# boilerroom.net
KiCad netlist of a schematic drawn in EAGLE
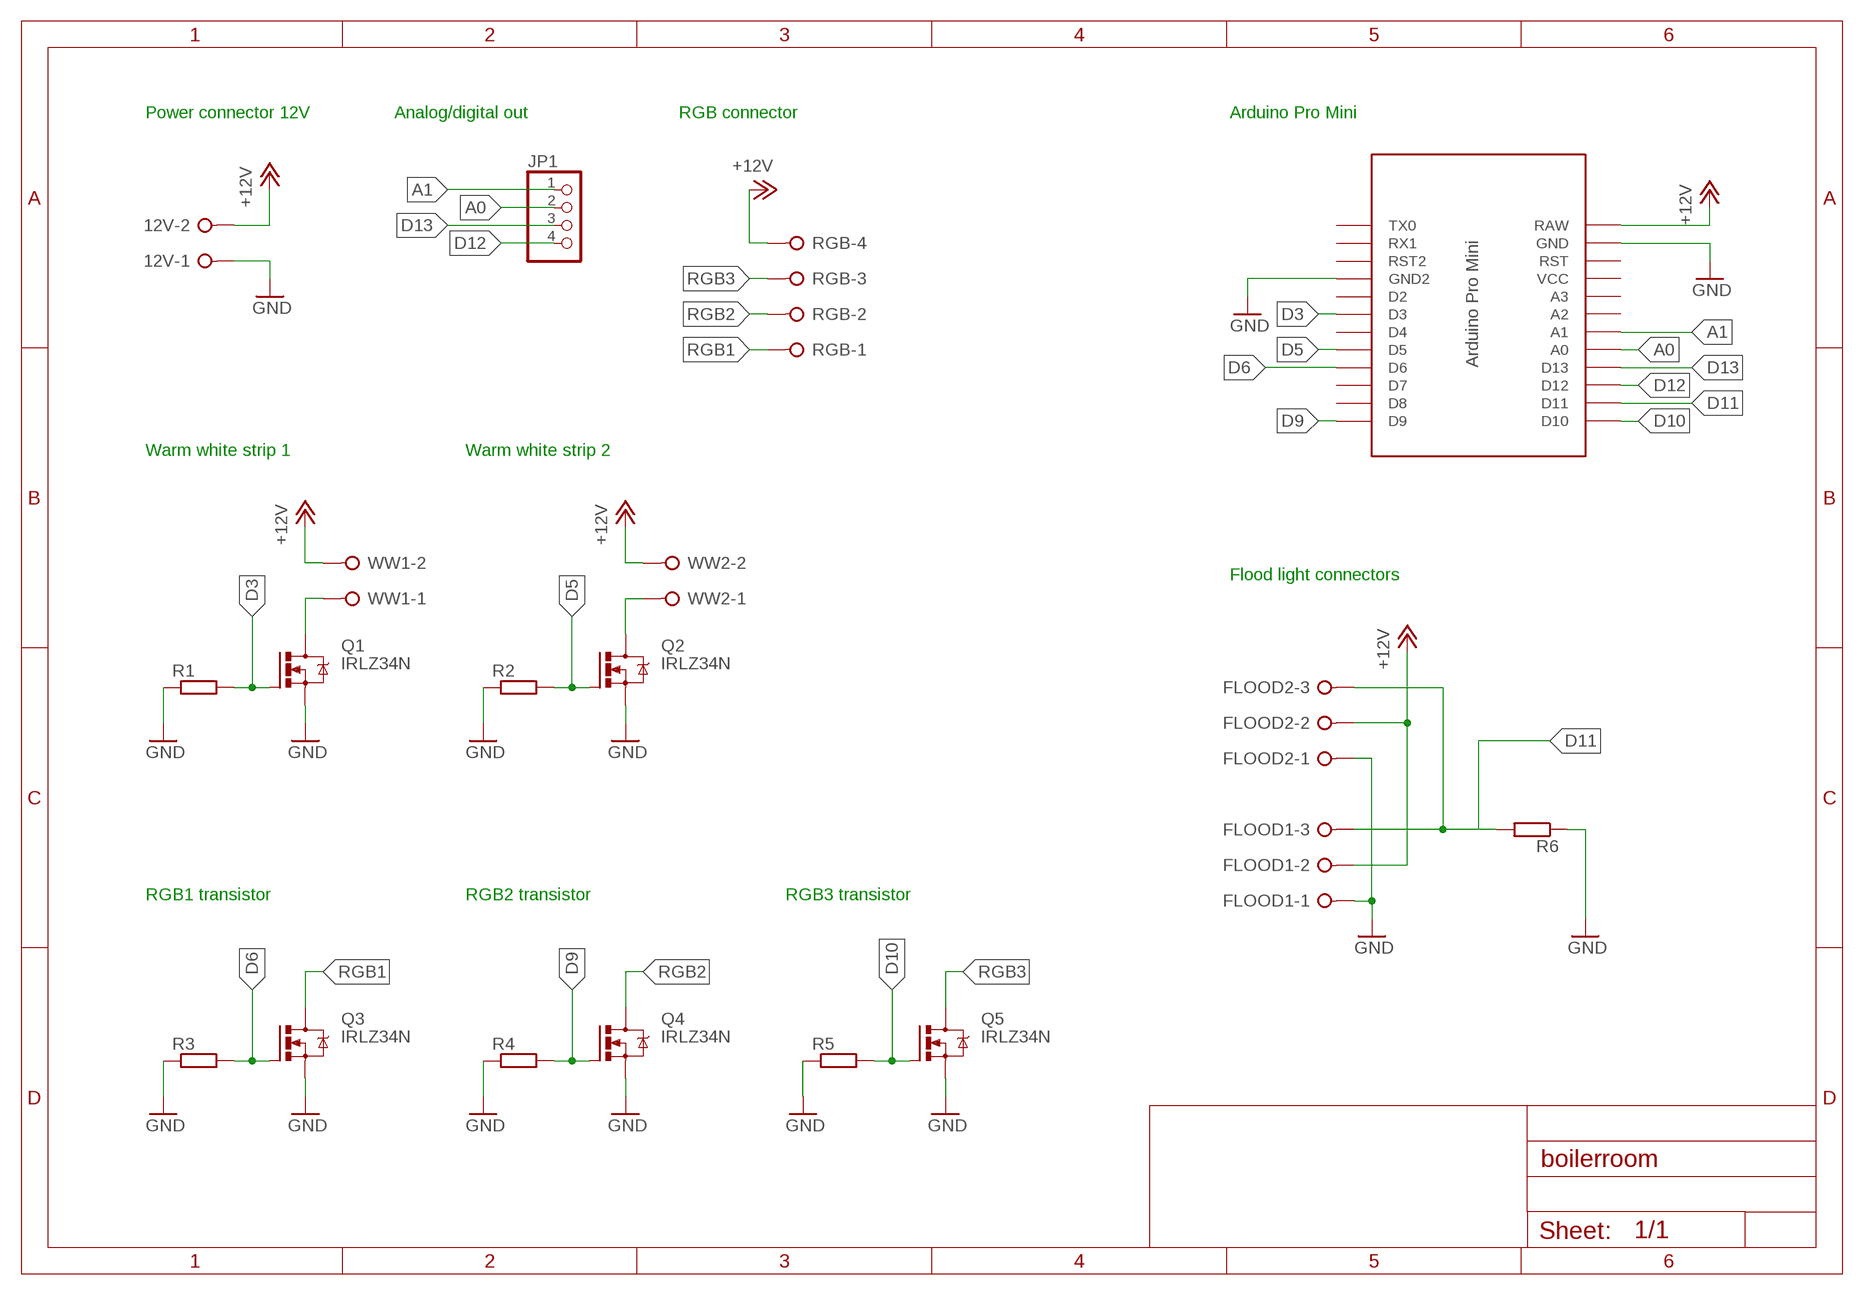
[diagram p0: schematic, sheet 1]

(export (version "E")
  (design (tool "Eeschema 10.0.6"))
  (components
    (comp (ref "12V")
      (value "W237-02P")
      (footprint "eagle-import:W237-132")
      (libsource (lib "eagle-import") (part "W237-02P"))
    )
    (comp (ref "FLOOD1")
      (value "W237-03P")
      (footprint "eagle-import:W237-133")
      (libsource (lib "eagle-import") (part "W237-03P"))
    )
    (comp (ref "FLOOD2")
      (value "W237-03P")
      (footprint "eagle-import:W237-133")
      (libsource (lib "eagle-import") (part "W237-03P"))
    )
    (comp (ref "JP1")
      (value "PINHD-1X4")
      (footprint "eagle-import:1X04")
      (libsource (lib "eagle-import") (part "PINHD-1X4"))
    )
    (comp (ref "Q1")
      (value "IRLZ34N")
      (footprint "eagle-import:TO220BV")
      (libsource (lib "eagle-import") (part "IRLZ44ZTO220BV"))
    )
    (comp (ref "Q2")
      (value "IRLZ34N")
      (footprint "eagle-import:TO220BV")
      (libsource (lib "eagle-import") (part "IRLZ44ZTO220BV"))
    )
    (comp (ref "Q3")
      (value "IRLZ34N")
      (footprint "eagle-import:TO220BV")
      (libsource (lib "eagle-import") (part "IRLZ44ZTO220BV"))
    )
    (comp (ref "Q4")
      (value "IRLZ34N")
      (footprint "eagle-import:TO220BV")
      (libsource (lib "eagle-import") (part "IRLZ44ZTO220BV"))
    )
    (comp (ref "Q5")
      (value "IRLZ34N")
      (footprint "eagle-import:TO220BV")
      (libsource (lib "eagle-import") (part "IRLZ44ZTO220BV"))
    )
    (comp (ref "R1")
      (value "R-EU_0207/10")
      (footprint "eagle-import:0207_10")
      (libsource (lib "eagle-import") (part "R-EU_0207/10"))
    )
    (comp (ref "R2")
      (value "R-EU_0207/10")
      (footprint "eagle-import:0207_10")
      (libsource (lib "eagle-import") (part "R-EU_0207/10"))
    )
    (comp (ref "R3")
      (value "R-EU_0207/10")
      (footprint "eagle-import:0207_10")
      (libsource (lib "eagle-import") (part "R-EU_0207/10"))
    )
    (comp (ref "R4")
      (value "R-EU_0207/10")
      (footprint "eagle-import:0207_10")
      (libsource (lib "eagle-import") (part "R-EU_0207/10"))
    )
    (comp (ref "R5")
      (value "R-EU_0207/10")
      (footprint "eagle-import:0207_10")
      (libsource (lib "eagle-import") (part "R-EU_0207/10"))
    )
    (comp (ref "R6")
      (value "R-EU_0207/10")
      (footprint "eagle-import:0207_10")
      (libsource (lib "eagle-import") (part "R-EU_0207/10"))
    )
    (comp (ref "RGB")
      (value "W237-04P")
      (footprint "eagle-import:W237-4P")
      (libsource (lib "eagle-import") (part "W237-04P"))
    )
    (comp (ref "U$2")
      (value "PRO-MINI-3V3")
      (footprint "eagle-import:PRO-MINI-3V3")
      (libsource (lib "eagle-import") (part "PRO-MINI-3V3"))
    )
    (comp (ref "WW1")
      (value "W237-02P")
      (footprint "eagle-import:W237-132")
      (libsource (lib "eagle-import") (part "W237-02P"))
    )
    (comp (ref "WW2")
      (value "W237-02P")
      (footprint "eagle-import:W237-132")
      (libsource (lib "eagle-import") (part "W237-02P"))
    )
  )
  (nets
    (net (code "1") (name "+12V") (class "Default")
      (node (ref "12V") (pin "2") (pinfunction "KL_2") (pintype "passive"))
      (node (ref "FLOOD1") (pin "2") (pinfunction "KL_2") (pintype "passive"))
      (node (ref "FLOOD2") (pin "2") (pinfunction "KL_2") (pintype "passive"))
      (node (ref "RGB") (pin "4") (pinfunction "KL_4") (pintype "passive"))
      (node (ref "U$2") (pin "RAW") (pinfunction "RAW_RAW") (pintype "power_in"))
      (node (ref "WW1") (pin "2") (pinfunction "KL_2") (pintype "passive"))
      (node (ref "WW2") (pin "2") (pinfunction "KL_2") (pintype "passive"))
    )
    (net (code "2") (name "A0") (class "Default")
      (node (ref "JP1") (pin "2") (pinfunction "2_2") (pintype "passive"))
      (node (ref "U$2") (pin "A0") (pinfunction "A0_A0") (pintype "bidirectional"))
    )
    (net (code "3") (name "A1") (class "Default")
      (node (ref "JP1") (pin "1") (pinfunction "1_1") (pintype "passive"))
      (node (ref "U$2") (pin "A1") (pinfunction "A1_A1") (pintype "bidirectional"))
    )
    (net (code "4") (name "D3") (class "Default")
      (node (ref "Q1") (pin "G") (pinfunction "G_G") (pintype "passive"))
      (node (ref "R1") (pin "2") (pinfunction "2_2") (pintype "passive"))
      (node (ref "U$2") (pin "D3") (pinfunction "D3_D3") (pintype "bidirectional"))
    )
    (net (code "5") (name "D5") (class "Default")
      (node (ref "Q2") (pin "G") (pinfunction "G_G") (pintype "passive"))
      (node (ref "R2") (pin "2") (pinfunction "2_2") (pintype "passive"))
      (node (ref "U$2") (pin "D5") (pinfunction "D5_D5") (pintype "bidirectional"))
    )
    (net (code "6") (name "D6") (class "Default")
      (node (ref "Q3") (pin "G") (pinfunction "G_G") (pintype "passive"))
      (node (ref "R3") (pin "2") (pinfunction "2_2") (pintype "passive"))
      (node (ref "U$2") (pin "D6") (pinfunction "D6_D6") (pintype "bidirectional"))
    )
    (net (code "7") (name "D9") (class "Default")
      (node (ref "Q4") (pin "G") (pinfunction "G_G") (pintype "passive"))
      (node (ref "R4") (pin "2") (pinfunction "2_2") (pintype "passive"))
      (node (ref "U$2") (pin "D9") (pinfunction "D9_D9") (pintype "bidirectional"))
    )
    (net (code "8") (name "D10") (class "Default")
      (node (ref "Q5") (pin "G") (pinfunction "G_G") (pintype "passive"))
      (node (ref "R5") (pin "2") (pinfunction "2_2") (pintype "passive"))
      (node (ref "U$2") (pin "D10") (pinfunction "D10_D10") (pintype "bidirectional"))
    )
    (net (code "9") (name "D11") (class "Default")
      (node (ref "FLOOD1") (pin "3") (pinfunction "KL_3") (pintype "passive"))
      (node (ref "FLOOD2") (pin "3") (pinfunction "KL_3") (pintype "passive"))
      (node (ref "R6") (pin "2") (pinfunction "2_2") (pintype "passive"))
      (node (ref "U$2") (pin "D11") (pinfunction "D11_D11") (pintype "bidirectional"))
    )
    (net (code "10") (name "D12") (class "Default")
      (node (ref "JP1") (pin "4") (pinfunction "4_4") (pintype "passive"))
      (node (ref "U$2") (pin "D12") (pinfunction "D12_D12") (pintype "bidirectional"))
    )
    (net (code "11") (name "D13") (class "Default")
      (node (ref "JP1") (pin "3") (pinfunction "3_3") (pintype "passive"))
      (node (ref "U$2") (pin "D13") (pinfunction "D13_D13") (pintype "bidirectional"))
    )
    (net (code "12") (name "GND") (class "Default")
      (node (ref "12V") (pin "1") (pinfunction "KL_1") (pintype "passive"))
      (node (ref "FLOOD1") (pin "1") (pinfunction "KL_1") (pintype "passive"))
      (node (ref "FLOOD2") (pin "1") (pinfunction "KL_1") (pintype "passive"))
      (node (ref "Q1") (pin "S") (pinfunction "S_S") (pintype "passive"))
      (node (ref "Q2") (pin "S") (pinfunction "S_S") (pintype "passive"))
      (node (ref "Q3") (pin "S") (pinfunction "S_S") (pintype "passive"))
      (node (ref "Q4") (pin "S") (pinfunction "S_S") (pintype "passive"))
      (node (ref "Q5") (pin "S") (pinfunction "S_S") (pintype "passive"))
      (node (ref "R1") (pin "1") (pinfunction "1_1") (pintype "passive"))
      (node (ref "R2") (pin "1") (pinfunction "1_1") (pintype "passive"))
      (node (ref "R3") (pin "1") (pinfunction "1_1") (pintype "passive"))
      (node (ref "R4") (pin "1") (pinfunction "1_1") (pintype "passive"))
      (node (ref "R5") (pin "1") (pinfunction "1_1") (pintype "passive"))
      (node (ref "R6") (pin "1") (pinfunction "1_1") (pintype "passive"))
      (node (ref "U$2") (pin "GND") (pinfunction "GND_GND") (pintype "input"))
      (node (ref "U$2") (pin "GND1") (pinfunction "GND2_GND1") (pintype "bidirectional"))
    )
    (net (code "13") (name "Net-(WW1A-KL)") (class "Default")
      (node (ref "Q1") (pin "D") (pinfunction "D_D") (pintype "passive"))
      (node (ref "WW1") (pin "1") (pinfunction "KL_1") (pintype "passive"))
    )
    (net (code "14") (name "Net-(WW2A-KL)") (class "Default")
      (node (ref "Q2") (pin "D") (pinfunction "D_D") (pintype "passive"))
      (node (ref "WW2") (pin "1") (pinfunction "KL_1") (pintype "passive"))
    )
    (net (code "15") (name "RGB1") (class "Default")
      (node (ref "Q3") (pin "D") (pinfunction "D_D") (pintype "passive"))
      (node (ref "RGB") (pin "1") (pinfunction "KL_1") (pintype "passive"))
    )
    (net (code "16") (name "RGB2") (class "Default")
      (node (ref "Q4") (pin "D") (pinfunction "D_D") (pintype "passive"))
      (node (ref "RGB") (pin "2") (pinfunction "KL_2") (pintype "passive"))
    )
    (net (code "17") (name "RGB3") (class "Default")
      (node (ref "Q5") (pin "D") (pinfunction "D_D") (pintype "passive"))
      (node (ref "RGB") (pin "3") (pinfunction "KL_3") (pintype "passive"))
    )
    (net (code "18") (name "unconnected-(U$2-PadA2)") (class "Default")
      (node (ref "U$2") (pin "A2") (pinfunction "A2_A2") (pintype "bidirectional"))
    )
    (net (code "19") (name "unconnected-(U$2-PadA3)") (class "Default")
      (node (ref "U$2") (pin "A3") (pinfunction "A3_A3") (pintype "bidirectional"))
    )
    (net (code "20") (name "unconnected-(U$2-PadD2)") (class "Default")
      (node (ref "U$2") (pin "D2") (pinfunction "D2_D2") (pintype "bidirectional"))
    )
    (net (code "21") (name "unconnected-(U$2-PadD4)") (class "Default")
      (node (ref "U$2") (pin "D4") (pinfunction "D4_D4") (pintype "bidirectional"))
    )
    (net (code "22") (name "unconnected-(U$2-PadD7)") (class "Default")
      (node (ref "U$2") (pin "D7") (pinfunction "D7_D7") (pintype "bidirectional"))
    )
    (net (code "23") (name "unconnected-(U$2-PadD8)") (class "Default")
      (node (ref "U$2") (pin "D8") (pinfunction "D8_D8") (pintype "bidirectional"))
    )
    (net (code "24") (name "unconnected-(U$2-PadRST)") (class "Default")
      (node (ref "U$2") (pin "RST") (pinfunction "RST_RST") (pintype "bidirectional"))
    )
    (net (code "25") (name "unconnected-(U$2-PadRX1)") (class "Default")
      (node (ref "U$2") (pin "RX1") (pinfunction "RX1_RX1") (pintype "bidirectional"))
    )
    (net (code "26") (name "unconnected-(U$2-PadTX0)") (class "Default")
      (node (ref "U$2") (pin "TX0") (pinfunction "TX0_TX0") (pintype "bidirectional"))
    )
    (net (code "27") (name "unconnected-(U$2-PadVCC)") (class "Default")
      (node (ref "U$2") (pin "VCC") (pinfunction "VCC_VCC") (pintype "bidirectional"))
    )
    (net (code "28") (name "unconnected-(U$2-RST2-PadRST1)") (class "Default")
      (node (ref "U$2") (pin "RST1") (pinfunction "RST2_RST1") (pintype "bidirectional"))
    )
  )
)
